# Boost_NEW.net
KiCad netlist of a schematic drawn in EAGLE
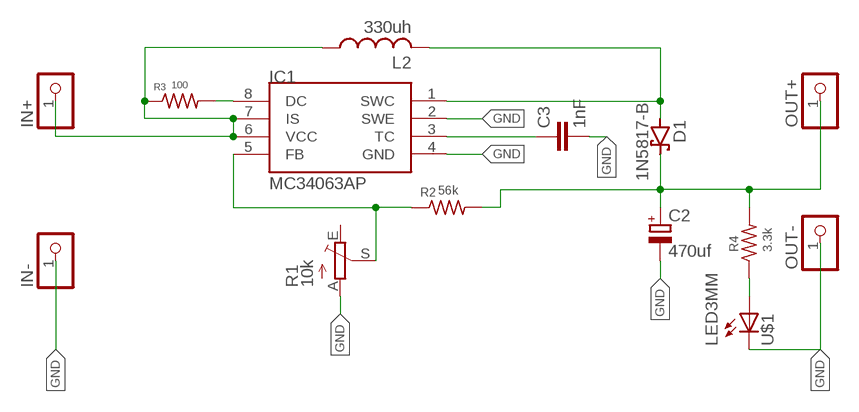
[diagram p0: schematic, sheet 1]

(export (version "E")
  (design (tool "Eeschema 10.0.6"))
  (components
    (comp (ref "C2")
      (value "470uf")
      (footprint "eagle-import:E3,5-8")
      (libsource (lib "eagle-import") (part "CAP_POL"))
    )
    (comp (ref "C3")
      (value "1nF")
      (footprint "eagle-import:C025-025X050")
      (libsource (lib "eagle-import") (part "CAPACITOR"))
    )
    (comp (ref "D1")
      (value "1N5817-B")
      (footprint "eagle-import:DO41-7.6")
      (libsource (lib "eagle-import") (part "1N5817-B"))
    )
    (comp (ref "IC1")
      (value "MC34063AP")
      (footprint "eagle-import:DIL08")
      (libsource (lib "eagle-import") (part "MC34063AP"))
    )
    (comp (ref "IN+")
      (value "PINHD-1X1")
      (footprint "eagle-import:1X01")
      (libsource (lib "eagle-import") (part "PINHD-1X1"))
    )
    (comp (ref "IN-")
      (value "PINHD-1X1")
      (footprint "eagle-import:1X01")
      (libsource (lib "eagle-import") (part "PINHD-1X1"))
    )
    (comp (ref "L2")
      (value "330uh")
      (footprint "eagle-import:0207_10")
      (libsource (lib "eagle-import") (part "L-US0207/10"))
    )
    (comp (ref "OUT+")
      (value "PINHD-1X1")
      (footprint "eagle-import:1X01")
      (libsource (lib "eagle-import") (part "PINHD-1X1"))
    )
    (comp (ref "OUT-")
      (value "PINHD-1X1")
      (footprint "eagle-import:1X01")
      (libsource (lib "eagle-import") (part "PINHD-1X1"))
    )
    (comp (ref "R1")
      (value "10k")
      (footprint "eagle-import:CA6V")
      (libsource (lib "eagle-import") (part "TRIM_EU-CA6V"))
    )
    (comp (ref "R2")
      (value "56k")
      (footprint "eagle-import:0204_7")
      (libsource (lib "eagle-import") (part "RES-7"))
    )
    (comp (ref "R3")
      (value "100")
      (footprint "eagle-import:0204_7")
      (libsource (lib "eagle-import") (part "RES-7"))
    )
    (comp (ref "R4")
      (value "3.3k")
      (footprint "eagle-import:0204_7")
      (libsource (lib "eagle-import") (part "RES-7"))
    )
    (comp (ref "U$1")
      (value "LED3MM")
      (footprint "eagle-import:LED3MM")
      (libsource (lib "eagle-import") (part "LED3MM"))
    )
  )
  (nets
    (net (code "1") (name "GND") (class "Default")
      (node (ref "C2") (pin "-") (pinfunction "-_-") (pintype "passive"))
      (node (ref "C3") (pin "2") (pinfunction "2_2") (pintype "passive"))
      (node (ref "IC1") (pin "2") (pinfunction "SWE_2") (pintype "passive"))
      (node (ref "IC1") (pin "4") (pinfunction "GND_4") (pintype "passive"))
      (node (ref "IN-") (pin "1") (pinfunction "1_1") (pintype "passive"))
      (node (ref "OUT-") (pin "1") (pinfunction "1_1") (pintype "passive"))
      (node (ref "R1") (pin "A") (pinfunction "A_A") (pintype "passive"))
      (node (ref "U$1") (pin "K") (pinfunction "C_K") (pintype "passive"))
    )
    (net (code "2") (name "Net-(C2-Pad+)") (class "Default")
      (node (ref "C2") (pin "+") (pinfunction "+_+") (pintype "passive"))
      (node (ref "D1") (pin "C") (pinfunction "C_C") (pintype "passive"))
      (node (ref "OUT+") (pin "1") (pinfunction "1_1") (pintype "passive"))
      (node (ref "R2") (pin "2") (pinfunction "2_2") (pintype "passive"))
      (node (ref "R4") (pin "2") (pinfunction "2_2") (pintype "passive"))
    )
    (net (code "3") (name "Net-(IC1-DC)") (class "Default")
      (node (ref "IC1") (pin "8") (pinfunction "DC_8") (pintype "passive"))
      (node (ref "R3") (pin "2") (pinfunction "2_2") (pintype "passive"))
    )
    (net (code "4") (name "Net-(IC1-FB)") (class "Default")
      (node (ref "IC1") (pin "5") (pinfunction "FB_5") (pintype "passive"))
      (node (ref "R1") (pin "S") (pinfunction "S_S") (pintype "passive"))
      (node (ref "R2") (pin "1") (pinfunction "1_1") (pintype "passive"))
    )
    (net (code "5") (name "Net-(IC1-IS)") (class "Default")
      (node (ref "IC1") (pin "6") (pinfunction "VCC_6") (pintype "passive"))
      (node (ref "IC1") (pin "7") (pinfunction "IS_7") (pintype "passive"))
      (node (ref "IN+") (pin "1") (pinfunction "1_1") (pintype "passive"))
      (node (ref "L2") (pin "1") (pinfunction "1_1") (pintype "passive"))
      (node (ref "R3") (pin "1") (pinfunction "1_1") (pintype "passive"))
    )
    (net (code "6") (name "Net-(IC1-SWC)") (class "Default")
      (node (ref "D1") (pin "A") (pinfunction "A_A") (pintype "passive"))
      (node (ref "IC1") (pin "1") (pinfunction "SWC_1") (pintype "passive"))
      (node (ref "L2") (pin "2") (pinfunction "2_2") (pintype "passive"))
    )
    (net (code "7") (name "Net-(IC1-TC)") (class "Default")
      (node (ref "C3") (pin "1") (pinfunction "1_1") (pintype "passive"))
      (node (ref "IC1") (pin "3") (pinfunction "TC_3") (pintype "passive"))
    )
    (net (code "8") (name "Net-(R4-Pad1)") (class "Default")
      (node (ref "R4") (pin "1") (pinfunction "1_1") (pintype "passive"))
      (node (ref "U$1") (pin "A") (pinfunction "A_A") (pintype "passive"))
    )
    (net (code "9") (name "unconnected-(R1-PadE)") (class "Default")
      (node (ref "R1") (pin "E") (pinfunction "E_E") (pintype "passive"))
    )
  )
)
